# Sheild_Generator_-_Main_unit.net
KiCad netlist of a schematic drawn in EAGLE
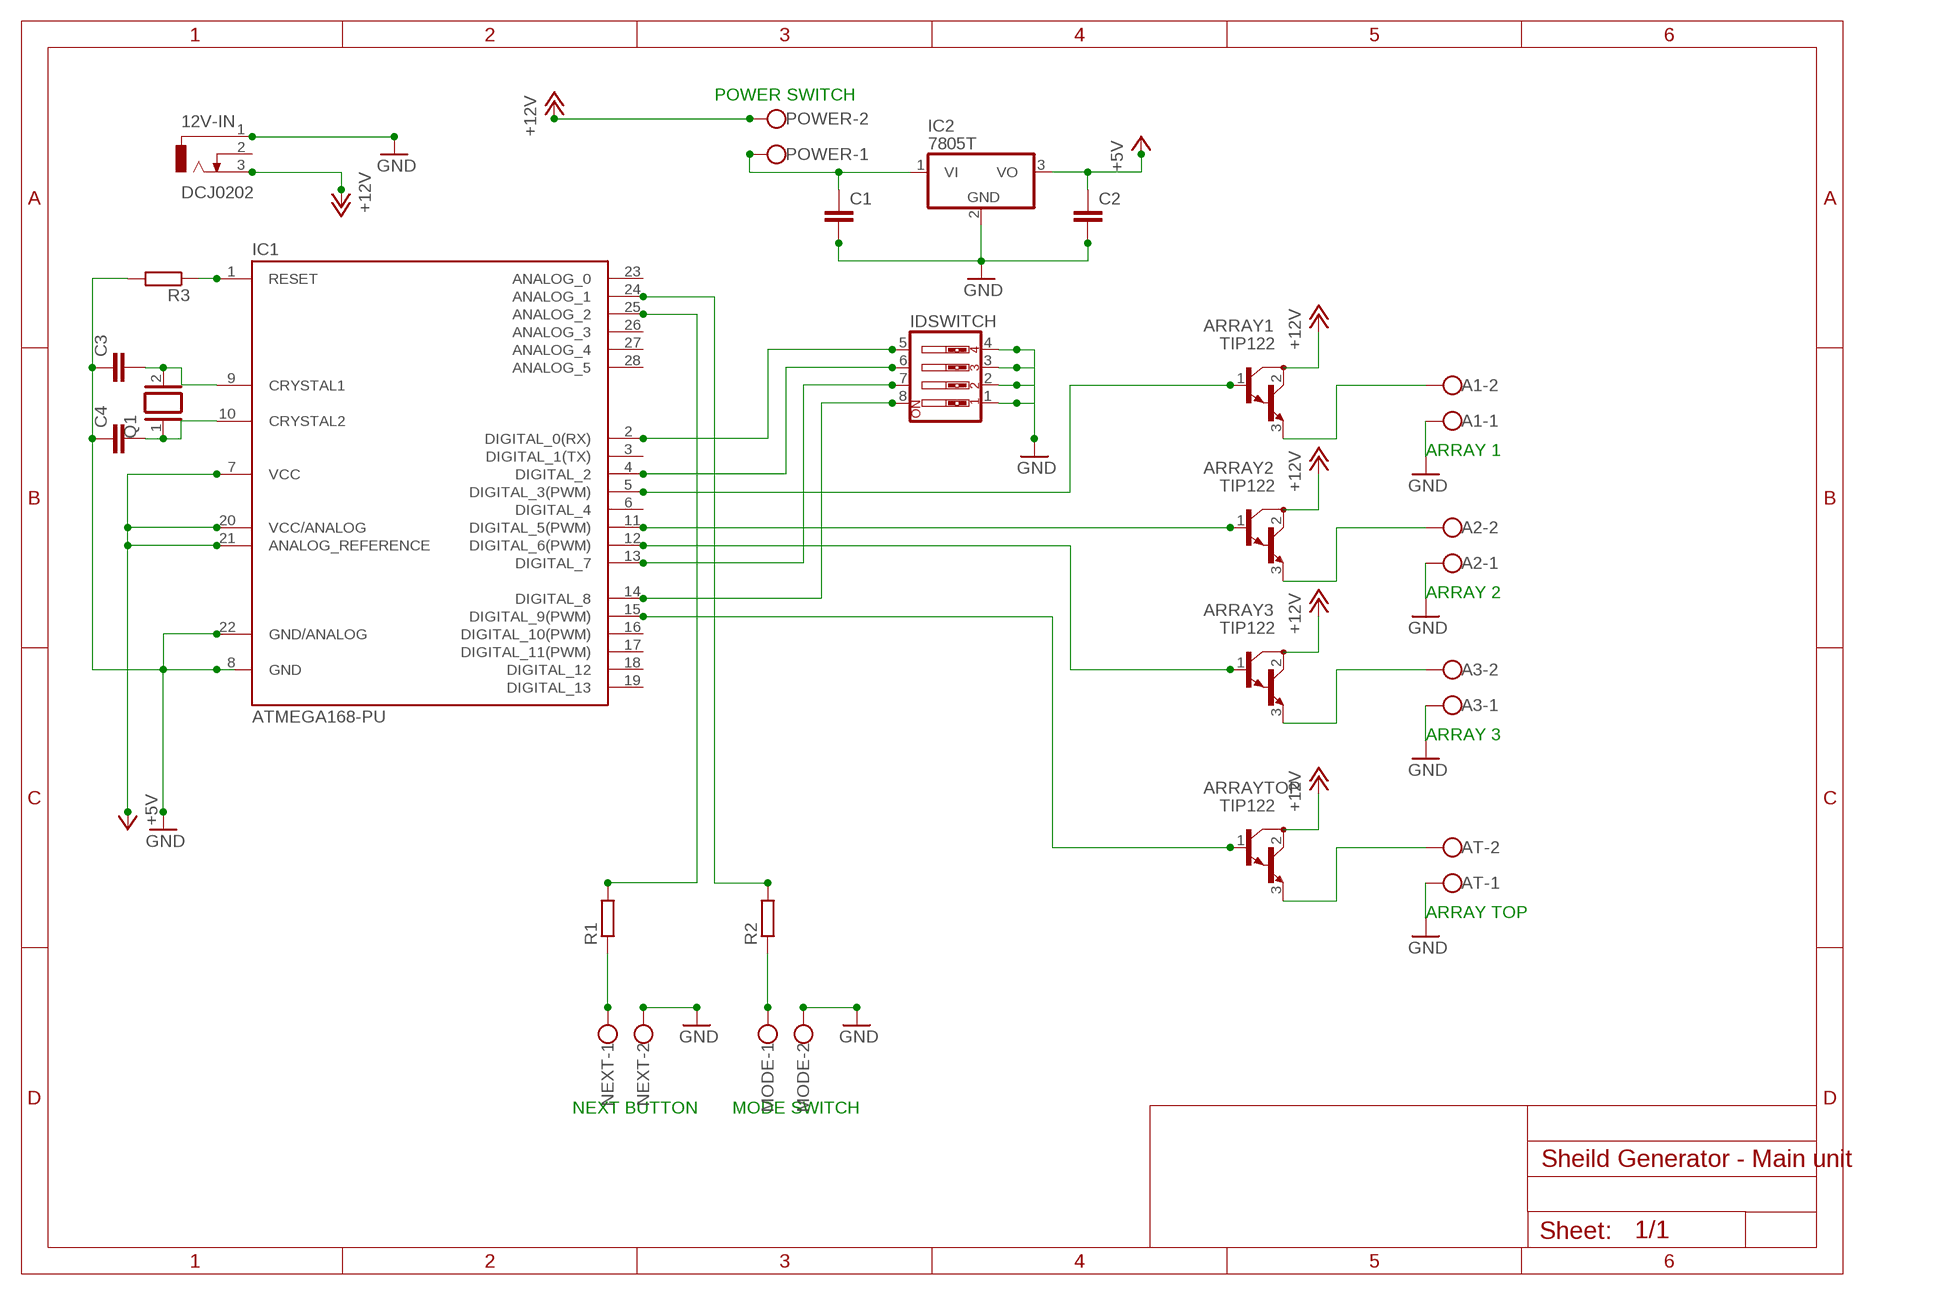
[diagram p0: schematic, sheet 1]

(export (version "E")
  (design (tool "Eeschema 10.0.6"))
  (components
    (comp (ref "12V-IN")
      (value "DCJ0202")
      (footprint "eagle-import:DCJ0202")
      (libsource (lib "eagle-import") (part "DCJ0202"))
    )
    (comp (ref "A1")
      (value "W237-102")
      (footprint "eagle-import:W237-102")
      (fields (field (name "MPN") "237-102"))
      (libsource (lib "eagle-import") (part "W237-102"))
    )
    (comp (ref "A2")
      (value "W237-102")
      (footprint "eagle-import:W237-102")
      (fields (field (name "MPN") "237-102"))
      (libsource (lib "eagle-import") (part "W237-102"))
    )
    (comp (ref "A3")
      (value "W237-102")
      (footprint "eagle-import:W237-102")
      (fields (field (name "MPN") "237-102"))
      (libsource (lib "eagle-import") (part "W237-102"))
    )
    (comp (ref "ARRAY1")
      (value "TIP122")
      (footprint "eagle-import:TO220")
      (libsource (lib "eagle-import") (part "TIP122"))
    )
    (comp (ref "ARRAY2")
      (value "TIP122")
      (footprint "eagle-import:TO220")
      (libsource (lib "eagle-import") (part "TIP122"))
    )
    (comp (ref "ARRAY3")
      (value "TIP122")
      (footprint "eagle-import:TO220")
      (libsource (lib "eagle-import") (part "TIP122"))
    )
    (comp (ref "ARRAYTOP")
      (value "TIP122")
      (footprint "eagle-import:TO220")
      (libsource (lib "eagle-import") (part "TIP122"))
    )
    (comp (ref "AT")
      (value "W237-102")
      (footprint "eagle-import:W237-102")
      (fields (field (name "MPN") "237-102"))
      (libsource (lib "eagle-import") (part "W237-102"))
    )
    (comp (ref "C1")
      (value "C-EU025-024X044")
      (footprint "eagle-import:C025-024X044")
      (libsource (lib "eagle-import") (part "C-EU025-024X044"))
    )
    (comp (ref "C2")
      (value "C-EU025-024X044")
      (footprint "eagle-import:C025-024X044")
      (libsource (lib "eagle-import") (part "C-EU025-024X044"))
    )
    (comp (ref "C3")
      (value "C-EU025-024X044")
      (footprint "eagle-import:C025-024X044")
      (libsource (lib "eagle-import") (part "C-EU025-024X044"))
    )
    (comp (ref "C4")
      (value "C-EU025-024X044")
      (footprint "eagle-import:C025-024X044")
      (libsource (lib "eagle-import") (part "C-EU025-024X044"))
    )
    (comp (ref "IC1")
      (value "ATMEGA168-PU")
      (footprint "eagle-import:DIL28-3")
      (libsource (lib "eagle-import") (part "ATMEGA168-PU"))
    )
    (comp (ref "IC2")
      (value "7805T")
      (footprint "eagle-import:TO220H")
      (libsource (lib "eagle-import") (part "78T05"))
    )
    (comp (ref "IDSWITCH")
      (value "SW_DIP-4")
      (footprint "eagle-import:EDG-04")
      (libsource (lib "eagle-import") (part "SW_DIP-4"))
    )
    (comp (ref "MODE")
      (value "W237-102")
      (footprint "eagle-import:W237-102")
      (fields (field (name "MPN") "237-102"))
      (libsource (lib "eagle-import") (part "W237-102"))
    )
    (comp (ref "NEXT")
      (value "W237-102")
      (footprint "eagle-import:W237-102")
      (fields (field (name "MPN") "237-102"))
      (libsource (lib "eagle-import") (part "W237-102"))
    )
    (comp (ref "POWER")
      (value "W237-102")
      (footprint "eagle-import:W237-102")
      (fields (field (name "MPN") "237-102"))
      (libsource (lib "eagle-import") (part "W237-102"))
    )
    (comp (ref "Q1")
      (value "XTAL/S")
      (footprint "eagle-import:QS")
      (libsource (lib "eagle-import") (part "XTAL/S"))
    )
    (comp (ref "R1")
      (value "R-EU_0204/7")
      (footprint "eagle-import:0204_7")
      (libsource (lib "eagle-import") (part "R-EU_0204/7"))
    )
    (comp (ref "R2")
      (value "R-EU_0204/7")
      (footprint "eagle-import:0204_7")
      (libsource (lib "eagle-import") (part "R-EU_0204/7"))
    )
    (comp (ref "R3")
      (value "R-EU_0204/7")
      (footprint "eagle-import:0204_7")
      (libsource (lib "eagle-import") (part "R-EU_0204/7"))
    )
  )
  (nets
    (net (code "1") (name "+5V") (class "Default")
      (node (ref "C2") (pin "1") (pinfunction "1_1") (pintype "passive"))
      (node (ref "IC1") (pin "20") (pinfunction "VCC/ANALOG_20") (pintype "passive"))
      (node (ref "IC1") (pin "21") (pinfunction "ANALOG_REFERENCE_21") (pintype "passive"))
      (node (ref "IC1") (pin "7") (pinfunction "VCC_7") (pintype "power_in"))
      (node (ref "IC2") (pin "3") (pinfunction "VO_3") (pintype "passive"))
    )
    (net (code "2") (name "+12V") (class "Default")
      (node (ref "12V-IN") (pin "3") (pinfunction "3_3") (pintype "passive"))
      (node (ref "ARRAY1") (pin "2") (pinfunction "C_2") (pintype "passive"))
      (node (ref "ARRAY2") (pin "2") (pinfunction "C_2") (pintype "passive"))
      (node (ref "ARRAY3") (pin "2") (pinfunction "C_2") (pintype "passive"))
      (node (ref "ARRAYTOP") (pin "2") (pinfunction "C_2") (pintype "passive"))
      (node (ref "POWER") (pin "2") (pinfunction "KL_2") (pintype "passive"))
    )
    (net (code "3") (name "GND") (class "Default")
      (node (ref "12V-IN") (pin "1") (pinfunction "1_1") (pintype "passive"))
      (node (ref "A1") (pin "1") (pinfunction "KL_1") (pintype "passive"))
      (node (ref "A2") (pin "1") (pinfunction "KL_1") (pintype "passive"))
      (node (ref "A3") (pin "1") (pinfunction "KL_1") (pintype "passive"))
      (node (ref "AT") (pin "1") (pinfunction "KL_1") (pintype "passive"))
      (node (ref "C1") (pin "2") (pinfunction "2_2") (pintype "passive"))
      (node (ref "C2") (pin "2") (pinfunction "2_2") (pintype "passive"))
      (node (ref "C3") (pin "1") (pinfunction "1_1") (pintype "passive"))
      (node (ref "C4") (pin "1") (pinfunction "1_1") (pintype "passive"))
      (node (ref "IC1") (pin "22") (pinfunction "GND/ANALOG_22") (pintype "power_in"))
      (node (ref "IC1") (pin "8") (pinfunction "GND_8") (pintype "power_in"))
      (node (ref "IC2") (pin "2") (pinfunction "GND_2") (pintype "passive"))
      (node (ref "IDSWITCH") (pin "1") (pinfunction "1_1") (pintype "passive"))
      (node (ref "IDSWITCH") (pin "2") (pinfunction "2_2") (pintype "passive"))
      (node (ref "IDSWITCH") (pin "3") (pinfunction "3_3") (pintype "passive"))
      (node (ref "IDSWITCH") (pin "4") (pinfunction "4_4") (pintype "passive"))
      (node (ref "MODE") (pin "2") (pinfunction "KL_2") (pintype "passive"))
      (node (ref "NEXT") (pin "2") (pinfunction "KL_2") (pintype "passive"))
      (node (ref "R3") (pin "2") (pinfunction "2_2") (pintype "passive"))
    )
    (net (code "4") (name "Net-(A1B-KL)") (class "Default")
      (node (ref "A1") (pin "2") (pinfunction "KL_2") (pintype "passive"))
      (node (ref "ARRAY1") (pin "3") (pinfunction "E_3") (pintype "passive"))
    )
    (net (code "5") (name "Net-(A2B-KL)") (class "Default")
      (node (ref "A2") (pin "2") (pinfunction "KL_2") (pintype "passive"))
      (node (ref "ARRAY2") (pin "3") (pinfunction "E_3") (pintype "passive"))
    )
    (net (code "6") (name "Net-(A3B-KL)") (class "Default")
      (node (ref "A3") (pin "2") (pinfunction "KL_2") (pintype "passive"))
      (node (ref "ARRAY3") (pin "3") (pinfunction "E_3") (pintype "passive"))
    )
    (net (code "7") (name "Net-(ARRAY1-B)") (class "Default")
      (node (ref "ARRAY1") (pin "1") (pinfunction "B_1") (pintype "passive"))
      (node (ref "IC1") (pin "5") (pinfunction "DIGITAL_3(PWM)_5") (pintype "bidirectional"))
    )
    (net (code "8") (name "Net-(ARRAY2-B)") (class "Default")
      (node (ref "ARRAY2") (pin "1") (pinfunction "B_1") (pintype "passive"))
      (node (ref "IC1") (pin "11") (pinfunction "DIGITAL_5(PWM)_11") (pintype "bidirectional"))
    )
    (net (code "9") (name "Net-(ARRAY3-B)") (class "Default")
      (node (ref "ARRAY3") (pin "1") (pinfunction "B_1") (pintype "passive"))
      (node (ref "IC1") (pin "12") (pinfunction "DIGITAL_6(PWM)_12") (pintype "bidirectional"))
    )
    (net (code "10") (name "Net-(ARRAYTOP-B)") (class "Default")
      (node (ref "ARRAYTOP") (pin "1") (pinfunction "B_1") (pintype "passive"))
      (node (ref "IC1") (pin "15") (pinfunction "DIGITAL_9(PWM)_15") (pintype "bidirectional"))
    )
    (net (code "11") (name "Net-(ARRAYTOP-E)") (class "Default")
      (node (ref "ARRAYTOP") (pin "3") (pinfunction "E_3") (pintype "passive"))
      (node (ref "AT") (pin "2") (pinfunction "KL_2") (pintype "passive"))
    )
    (net (code "12") (name "Net-(IC1-ANALOG_1)") (class "Default")
      (node (ref "IC1") (pin "24") (pinfunction "ANALOG_1_24") (pintype "bidirectional"))
      (node (ref "R2") (pin "2") (pinfunction "2_2") (pintype "passive"))
    )
    (net (code "13") (name "Net-(IC1-ANALOG_2)") (class "Default")
      (node (ref "IC1") (pin "25") (pinfunction "ANALOG_2_25") (pintype "bidirectional"))
      (node (ref "R1") (pin "2") (pinfunction "2_2") (pintype "passive"))
    )
    (net (code "14") (name "Net-(IC1-CRYSTAL1)") (class "Default")
      (node (ref "C3") (pin "2") (pinfunction "2_2") (pintype "passive"))
      (node (ref "IC1") (pin "9") (pinfunction "CRYSTAL1_9") (pintype "bidirectional"))
      (node (ref "Q1") (pin "2") (pinfunction "2_2") (pintype "passive"))
    )
    (net (code "15") (name "Net-(IC1-CRYSTAL2)") (class "Default")
      (node (ref "C4") (pin "2") (pinfunction "2_2") (pintype "passive"))
      (node (ref "IC1") (pin "10") (pinfunction "CRYSTAL2_10") (pintype "bidirectional"))
      (node (ref "Q1") (pin "1") (pinfunction "1_1") (pintype "passive"))
    )
    (net (code "16") (name "Net-(IC1-DIGITAL_0(RX))") (class "Default")
      (node (ref "IC1") (pin "2") (pinfunction "DIGITAL_0(RX)_2") (pintype "bidirectional"))
      (node (ref "IDSWITCH") (pin "5") (pinfunction "5_5") (pintype "passive"))
    )
    (net (code "17") (name "Net-(IC1-DIGITAL_2)") (class "Default")
      (node (ref "IC1") (pin "4") (pinfunction "DIGITAL_2_4") (pintype "bidirectional"))
      (node (ref "IDSWITCH") (pin "6") (pinfunction "6_6") (pintype "passive"))
    )
    (net (code "18") (name "Net-(IC1-DIGITAL_7)") (class "Default")
      (node (ref "IC1") (pin "13") (pinfunction "DIGITAL_7_13") (pintype "bidirectional"))
      (node (ref "IDSWITCH") (pin "7") (pinfunction "7_7") (pintype "passive"))
    )
    (net (code "19") (name "Net-(IC1-DIGITAL_8)") (class "Default")
      (node (ref "IC1") (pin "14") (pinfunction "DIGITAL_8_14") (pintype "bidirectional"))
      (node (ref "IDSWITCH") (pin "8") (pinfunction "8_8") (pintype "passive"))
    )
    (net (code "20") (name "Net-(IC1-RESET)") (class "Default")
      (node (ref "IC1") (pin "1") (pinfunction "RESET_1") (pintype "bidirectional"))
      (node (ref "R3") (pin "1") (pinfunction "1_1") (pintype "passive"))
    )
    (net (code "21") (name "Net-(IC2-VI)") (class "Default")
      (node (ref "C1") (pin "1") (pinfunction "1_1") (pintype "passive"))
      (node (ref "IC2") (pin "1") (pinfunction "VI_1") (pintype "input"))
      (node (ref "POWER") (pin "1") (pinfunction "KL_1") (pintype "passive"))
    )
    (net (code "22") (name "Net-(MODEA-KL)") (class "Default")
      (node (ref "MODE") (pin "1") (pinfunction "KL_1") (pintype "passive"))
      (node (ref "R2") (pin "1") (pinfunction "1_1") (pintype "passive"))
    )
    (net (code "23") (name "Net-(NEXTA-KL)") (class "Default")
      (node (ref "NEXT") (pin "1") (pinfunction "KL_1") (pintype "passive"))
      (node (ref "R1") (pin "1") (pinfunction "1_1") (pintype "passive"))
    )
    (net (code "24") (name "unconnected-(12V-IN-Pad2)") (class "Default")
      (node (ref "12V-IN") (pin "2") (pinfunction "2_2") (pintype "passive"))
    )
    (net (code "25") (name "unconnected-(IC1-ANALOG_0-Pad23)") (class "Default")
      (node (ref "IC1") (pin "23") (pinfunction "ANALOG_0_23") (pintype "bidirectional"))
    )
    (net (code "26") (name "unconnected-(IC1-ANALOG_3-Pad26)") (class "Default")
      (node (ref "IC1") (pin "26") (pinfunction "ANALOG_3_26") (pintype "bidirectional"))
    )
    (net (code "27") (name "unconnected-(IC1-ANALOG_4-Pad27)") (class "Default")
      (node (ref "IC1") (pin "27") (pinfunction "ANALOG_4_27") (pintype "bidirectional"))
    )
    (net (code "28") (name "unconnected-(IC1-ANALOG_5-Pad28)") (class "Default")
      (node (ref "IC1") (pin "28") (pinfunction "ANALOG_5_28") (pintype "bidirectional"))
    )
    (net (code "29") (name "unconnected-(IC1-DIGITAL_1(TX)-Pad3)") (class "Default")
      (node (ref "IC1") (pin "3") (pinfunction "DIGITAL_1(TX)_3") (pintype "bidirectional"))
    )
    (net (code "30") (name "unconnected-(IC1-DIGITAL_4-Pad6)") (class "Default")
      (node (ref "IC1") (pin "6") (pinfunction "DIGITAL_4_6") (pintype "bidirectional"))
    )
    (net (code "31") (name "unconnected-(IC1-DIGITAL_10(PWM)-Pad16)") (class "Default")
      (node (ref "IC1") (pin "16") (pinfunction "DIGITAL_10(PWM)_16") (pintype "bidirectional"))
    )
    (net (code "32") (name "unconnected-(IC1-DIGITAL_11(PWM)-Pad17)") (class "Default")
      (node (ref "IC1") (pin "17") (pinfunction "DIGITAL_11(PWM)_17") (pintype "bidirectional"))
    )
    (net (code "33") (name "unconnected-(IC1-DIGITAL_12-Pad18)") (class "Default")
      (node (ref "IC1") (pin "18") (pinfunction "DIGITAL_12_18") (pintype "bidirectional"))
    )
    (net (code "34") (name "unconnected-(IC1-DIGITAL_13-Pad19)") (class "Default")
      (node (ref "IC1") (pin "19") (pinfunction "DIGITAL_13_19") (pintype "bidirectional"))
    )
  )
)
